# WeatherStation.net
KiCad netlist of a schematic drawn in EasyEDA Pro
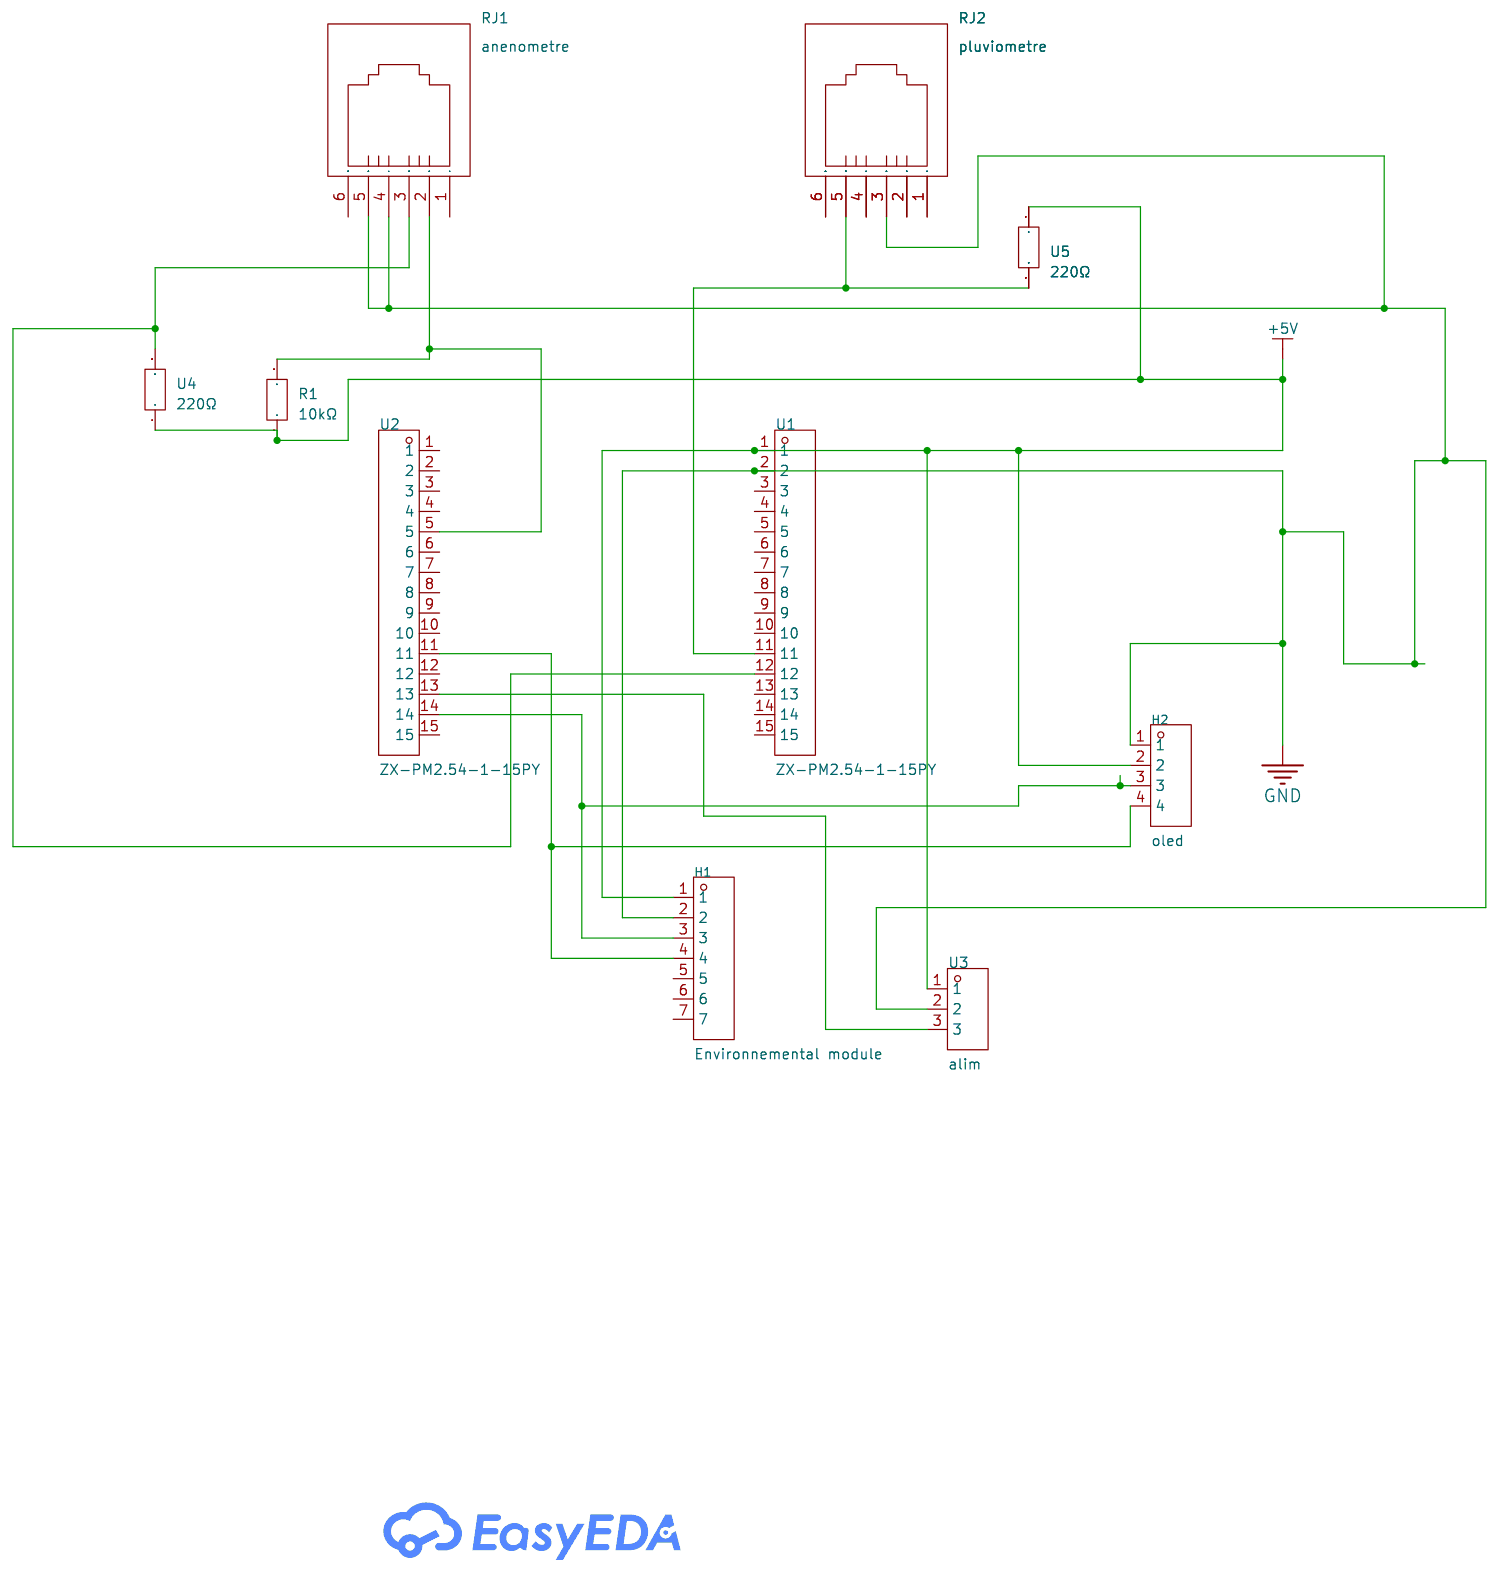
[diagram p0: schematic sheet]

(export (version "E")
  (design (tool "Eeschema 10.0.6"))
  (components
    (comp (ref "H1")
      (value "Environnemental module")
      (footprint "easyedapro:HDR-TH_7P-P2.54-V-F")
      (fields (field (name "Manufacturer") "XFCN(兴飞)"))
      (libsource (lib "easyedapro") (part "PM254V-11-07-H85"))
    )
    (comp (ref "H2")
      (value "oled")
      (footprint "easyedapro:HDR-TH_4P-P2.54-V-F")
      (fields (field (name "Manufacturer") "BOOMELE(博穆精密)"))
      (libsource (lib "easyedapro") (part "2.54-1*4P母"))
    )
    (comp (ref "R1")
      (value "10kΩ")
      (footprint "easyedapro:RES-TH_BD2.7-L6.2-P10.20-D0.4")
      (fields (field (name "Manufacturer Part") "MF1/4W-10K±1%-ST52") (field (name "Manufacturer") "VO(翔胜)"))
      (libsource (lib "easyedapro") (part "MF1/4W-10K±1%-ST52"))
    )
    (comp (ref "RJ1")
      (value "anenometre")
      (footprint "easyedapro:RJ11-TH_DS1133-S60BPX")
      (description "Connector Type:RJ12 Jack Number of Ports:1 LED:- Shielding:- Ratings:-")
      (fields (field (name "Manufacturer") "CONNFLY"))
      (libsource (lib "easyedapro") (part "DS1133-S60BPX"))
    )
    (comp (ref "RJ2")
      (value "pluviometre")
      (footprint "easyedapro:RJ11-TH_DS1133-S60BPX")
      (description "Connector Type:RJ12 Jack Number of Ports:1 LED:- Shielding:- Ratings:-")
      (fields (field (name "Manufacturer") "CONNFLY"))
      (libsource (lib "easyedapro") (part "DS1133-S60BPX"))
    )
    (comp (ref "U1")
      (value "ZX-PM2.54-1-15PY")
      (footprint "easyedapro:HDR-TH_15P-P2.54-V-F")
      (fields (field (name "Manufacturer") "Megastar(兆星)"))
      (libsource (lib "easyedapro") (part "ZX-PM2.54-1-15PY"))
    )
    (comp (ref "U2")
      (value "ZX-PM2.54-1-15PY")
      (footprint "easyedapro:HDR-TH_15P-P2.54-V-F")
      (fields (field (name "Manufacturer") "Megastar(兆星)"))
      (libsource (lib "easyedapro") (part "ZX-PM2.54-1-15PY"))
    )
    (comp (ref "U3")
      (value "alim")
      (footprint "easyedapro:CONN-TH_3P-P5.08_DB128L-5.08-3P-BK-S")
      (fields (field (name "Manufacturer") "DORABO(地博电气)"))
      (libsource (lib "easyedapro") (part "DB128L-5.08-3P-BK-S"))
    )
    (comp (ref "U4")
      (value "220Ω")
      (footprint "easyedapro:RES-TH_BD2.4-L6.3-P10.30-D0.6")
      (fields (field (name "Manufacturer Part") "MFR-25FBF52-220R") (field (name "Manufacturer") "YAGEO(国巨)"))
      (libsource (lib "easyedapro") (part "MFR-25FBF52-220R"))
    )
    (comp (ref "U5")
      (value "220Ω")
      (footprint "easyedapro:RES-TH_BD2.4-L6.3-P10.30-D0.6")
      (fields (field (name "Manufacturer Part") "MFR-25FBF52-220R") (field (name "Manufacturer") "YAGEO(国巨)"))
      (libsource (lib "easyedapro") (part "MFR-25FBF52-220R"))
    )
  )
  (nets
    (net (code "1") (name "+5V") (class "Default")
      (node (ref "H1") (pin "1") (pinfunction "1_1") (pintype "input"))
      (node (ref "H2") (pin "2") (pinfunction "2_2") (pintype "input"))
      (node (ref "R1") (pin "1") (pinfunction "1_1") (pintype "unspecified"))
      (node (ref "U1") (pin "1") (pinfunction "1_1") (pintype "unspecified"))
      (node (ref "U3") (pin "1") (pinfunction "1_1") (pintype "unspecified"))
      (node (ref "U4") (pin "1") (pinfunction "1_1") (pintype "unspecified"))
      (node (ref "U5") (pin "1") (pinfunction "1_1") (pintype "unspecified"))
    )
    (net (code "2") (name "GND") (class "Default")
      (node (ref "H1") (pin "2") (pinfunction "2_2") (pintype "input"))
      (node (ref "H2") (pin "1") (pinfunction "1_1") (pintype "input"))
      (node (ref "RJ1") (pin "4") (pinfunction "4_4") (pintype "unspecified"))
      (node (ref "RJ1") (pin "5") (pinfunction "5_5") (pintype "unspecified"))
      (node (ref "RJ2") (pin "3") (pinfunction "3_3") (pintype "unspecified"))
      (node (ref "U1") (pin "2") (pinfunction "2_2") (pintype "unspecified"))
      (node (ref "U3") (pin "2") (pinfunction "2_2") (pintype "unspecified"))
    )
    (net (code "3") (name "Net-(H1-Pad3)") (class "Default")
      (node (ref "H1") (pin "3") (pinfunction "3_3") (pintype "input"))
      (node (ref "H2") (pin "3") (pinfunction "3_3") (pintype "input"))
      (node (ref "U2") (pin "14") (pinfunction "14_14") (pintype "unspecified"))
    )
    (net (code "4") (name "Net-(H1-Pad4)") (class "Default")
      (node (ref "H1") (pin "4") (pinfunction "4_4") (pintype "input"))
      (node (ref "H2") (pin "4") (pinfunction "4_4") (pintype "input"))
      (node (ref "U2") (pin "11") (pinfunction "11_11") (pintype "unspecified"))
    )
    (net (code "5") (name "Net-(R1-Pad2)") (class "Default")
      (node (ref "R1") (pin "2") (pinfunction "2_2") (pintype "unspecified"))
      (node (ref "RJ1") (pin "2") (pinfunction "2_2") (pintype "unspecified"))
      (node (ref "U2") (pin "5") (pinfunction "5_5") (pintype "unspecified"))
    )
    (net (code "6") (name "Net-(RJ1-Pad3)") (class "Default")
      (node (ref "RJ1") (pin "3") (pinfunction "3_3") (pintype "unspecified"))
      (node (ref "U1") (pin "12") (pinfunction "12_12") (pintype "unspecified"))
      (node (ref "U4") (pin "2") (pinfunction "2_2") (pintype "unspecified"))
    )
    (net (code "7") (name "Net-(RJ2-Pad5)") (class "Default")
      (node (ref "RJ2") (pin "5") (pinfunction "5_5") (pintype "unspecified"))
      (node (ref "U1") (pin "11") (pinfunction "11_11") (pintype "unspecified"))
      (node (ref "U5") (pin "2") (pinfunction "2_2") (pintype "unspecified"))
    )
    (net (code "8") (name "Net-(U2-Pad13)") (class "Default")
      (node (ref "U2") (pin "13") (pinfunction "13_13") (pintype "unspecified"))
      (node (ref "U3") (pin "3") (pinfunction "3_3") (pintype "unspecified"))
    )
    (net (code "9") (name "unconnected-(H1-Pad5)") (class "Default")
      (node (ref "H1") (pin "5") (pinfunction "5_5") (pintype "input"))
    )
    (net (code "10") (name "unconnected-(H1-Pad6)") (class "Default")
      (node (ref "H1") (pin "6") (pinfunction "6_6") (pintype "input"))
    )
    (net (code "11") (name "unconnected-(H1-Pad7)") (class "Default")
      (node (ref "H1") (pin "7") (pinfunction "7_7") (pintype "input"))
    )
    (net (code "12") (name "unconnected-(RJ1-Pad1)") (class "Default")
      (node (ref "RJ1") (pin "1") (pinfunction "1_1") (pintype "unspecified"))
    )
    (net (code "13") (name "unconnected-(RJ1-Pad6)") (class "Default")
      (node (ref "RJ1") (pin "6") (pinfunction "6_6") (pintype "unspecified"))
    )
    (net (code "14") (name "unconnected-(RJ2-Pad1)") (class "Default")
      (node (ref "RJ2") (pin "1") (pinfunction "1_1") (pintype "unspecified"))
    )
    (net (code "15") (name "unconnected-(RJ2-Pad2)") (class "Default")
      (node (ref "RJ2") (pin "2") (pinfunction "2_2") (pintype "unspecified"))
    )
    (net (code "16") (name "unconnected-(RJ2-Pad4)") (class "Default")
      (node (ref "RJ2") (pin "4") (pinfunction "4_4") (pintype "unspecified"))
    )
    (net (code "17") (name "unconnected-(RJ2-Pad6)") (class "Default")
      (node (ref "RJ2") (pin "6") (pinfunction "6_6") (pintype "unspecified"))
    )
    (net (code "18") (name "unconnected-(U1-Pad3)") (class "Default")
      (node (ref "U1") (pin "3") (pinfunction "3_3") (pintype "unspecified"))
    )
    (net (code "19") (name "unconnected-(U1-Pad4)") (class "Default")
      (node (ref "U1") (pin "4") (pinfunction "4_4") (pintype "unspecified"))
    )
    (net (code "20") (name "unconnected-(U1-Pad5)") (class "Default")
      (node (ref "U1") (pin "5") (pinfunction "5_5") (pintype "unspecified"))
    )
    (net (code "21") (name "unconnected-(U1-Pad6)") (class "Default")
      (node (ref "U1") (pin "6") (pinfunction "6_6") (pintype "unspecified"))
    )
    (net (code "22") (name "unconnected-(U1-Pad7)") (class "Default")
      (node (ref "U1") (pin "7") (pinfunction "7_7") (pintype "unspecified"))
    )
    (net (code "23") (name "unconnected-(U1-Pad8)") (class "Default")
      (node (ref "U1") (pin "8") (pinfunction "8_8") (pintype "unspecified"))
    )
    (net (code "24") (name "unconnected-(U1-Pad9)") (class "Default")
      (node (ref "U1") (pin "9") (pinfunction "9_9") (pintype "unspecified"))
    )
    (net (code "25") (name "unconnected-(U1-Pad10)") (class "Default")
      (node (ref "U1") (pin "10") (pinfunction "10_10") (pintype "unspecified"))
    )
    (net (code "26") (name "unconnected-(U1-Pad13)") (class "Default")
      (node (ref "U1") (pin "13") (pinfunction "13_13") (pintype "unspecified"))
    )
    (net (code "27") (name "unconnected-(U1-Pad14)") (class "Default")
      (node (ref "U1") (pin "14") (pinfunction "14_14") (pintype "unspecified"))
    )
    (net (code "28") (name "unconnected-(U1-Pad15)") (class "Default")
      (node (ref "U1") (pin "15") (pinfunction "15_15") (pintype "unspecified"))
    )
    (net (code "29") (name "unconnected-(U2-Pad1)") (class "Default")
      (node (ref "U2") (pin "1") (pinfunction "1_1") (pintype "unspecified"))
    )
    (net (code "30") (name "unconnected-(U2-Pad2)") (class "Default")
      (node (ref "U2") (pin "2") (pinfunction "2_2") (pintype "unspecified"))
    )
    (net (code "31") (name "unconnected-(U2-Pad3)") (class "Default")
      (node (ref "U2") (pin "3") (pinfunction "3_3") (pintype "unspecified"))
    )
    (net (code "32") (name "unconnected-(U2-Pad4)") (class "Default")
      (node (ref "U2") (pin "4") (pinfunction "4_4") (pintype "unspecified"))
    )
    (net (code "33") (name "unconnected-(U2-Pad6)") (class "Default")
      (node (ref "U2") (pin "6") (pinfunction "6_6") (pintype "unspecified"))
    )
    (net (code "34") (name "unconnected-(U2-Pad7)") (class "Default")
      (node (ref "U2") (pin "7") (pinfunction "7_7") (pintype "unspecified"))
    )
    (net (code "35") (name "unconnected-(U2-Pad8)") (class "Default")
      (node (ref "U2") (pin "8") (pinfunction "8_8") (pintype "unspecified"))
    )
    (net (code "36") (name "unconnected-(U2-Pad9)") (class "Default")
      (node (ref "U2") (pin "9") (pinfunction "9_9") (pintype "unspecified"))
    )
    (net (code "37") (name "unconnected-(U2-Pad10)") (class "Default")
      (node (ref "U2") (pin "10") (pinfunction "10_10") (pintype "unspecified"))
    )
    (net (code "38") (name "unconnected-(U2-Pad12)") (class "Default")
      (node (ref "U2") (pin "12") (pinfunction "12_12") (pintype "unspecified"))
    )
    (net (code "39") (name "unconnected-(U2-Pad15)") (class "Default")
      (node (ref "U2") (pin "15") (pinfunction "15_15") (pintype "unspecified"))
    )
  )
)
